# Alpha-Num_Single.net
KiCad netlist of a schematic drawn in EAGLE
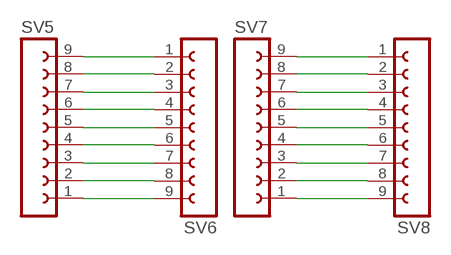
[diagram p0: schematic, sheet 1]

(export (version "E")
  (design (tool "Eeschema 10.0.6"))
  (components
    (comp (ref "SV5")
      (value "FE09-1")
      (footprint "eagle-import:FE09")
      (libsource (lib "eagle-import") (part "FE09-1"))
    )
    (comp (ref "SV6")
      (value "FE09-1")
      (footprint "eagle-import:FE09")
      (libsource (lib "eagle-import") (part "FE09-1"))
    )
    (comp (ref "SV7")
      (value "FE09-1")
      (footprint "eagle-import:FE09")
      (libsource (lib "eagle-import") (part "FE09-1"))
    )
    (comp (ref "SV8")
      (value "FE09-1")
      (footprint "eagle-import:FE09")
      (libsource (lib "eagle-import") (part "FE09-1"))
    )
  )
  (nets
    (net (code "1") (name "Net-(SV5-Pad1)") (class "Default")
      (node (ref "SV5") (pin "1") (pinfunction "1_1") (pintype "passive"))
      (node (ref "SV6") (pin "9") (pinfunction "9_9") (pintype "passive"))
    )
    (net (code "2") (name "Net-(SV5-Pad2)") (class "Default")
      (node (ref "SV5") (pin "2") (pinfunction "2_2") (pintype "passive"))
      (node (ref "SV6") (pin "8") (pinfunction "8_8") (pintype "passive"))
    )
    (net (code "3") (name "Net-(SV5-Pad3)") (class "Default")
      (node (ref "SV5") (pin "3") (pinfunction "3_3") (pintype "passive"))
      (node (ref "SV6") (pin "7") (pinfunction "7_7") (pintype "passive"))
    )
    (net (code "4") (name "Net-(SV5-Pad4)") (class "Default")
      (node (ref "SV5") (pin "4") (pinfunction "4_4") (pintype "passive"))
      (node (ref "SV6") (pin "6") (pinfunction "6_6") (pintype "passive"))
    )
    (net (code "5") (name "Net-(SV5-Pad5)") (class "Default")
      (node (ref "SV5") (pin "5") (pinfunction "5_5") (pintype "passive"))
      (node (ref "SV6") (pin "5") (pinfunction "5_5") (pintype "passive"))
    )
    (net (code "6") (name "Net-(SV5-Pad6)") (class "Default")
      (node (ref "SV5") (pin "6") (pinfunction "6_6") (pintype "passive"))
      (node (ref "SV6") (pin "4") (pinfunction "4_4") (pintype "passive"))
    )
    (net (code "7") (name "Net-(SV5-Pad7)") (class "Default")
      (node (ref "SV5") (pin "7") (pinfunction "7_7") (pintype "passive"))
      (node (ref "SV6") (pin "3") (pinfunction "3_3") (pintype "passive"))
    )
    (net (code "8") (name "Net-(SV5-Pad8)") (class "Default")
      (node (ref "SV5") (pin "8") (pinfunction "8_8") (pintype "passive"))
      (node (ref "SV6") (pin "2") (pinfunction "2_2") (pintype "passive"))
    )
    (net (code "9") (name "Net-(SV5-Pad9)") (class "Default")
      (node (ref "SV5") (pin "9") (pinfunction "9_9") (pintype "passive"))
      (node (ref "SV6") (pin "1") (pinfunction "1_1") (pintype "passive"))
    )
    (net (code "10") (name "Net-(SV7-Pad1)") (class "Default")
      (node (ref "SV7") (pin "1") (pinfunction "1_1") (pintype "passive"))
      (node (ref "SV8") (pin "9") (pinfunction "9_9") (pintype "passive"))
    )
    (net (code "11") (name "Net-(SV7-Pad2)") (class "Default")
      (node (ref "SV7") (pin "2") (pinfunction "2_2") (pintype "passive"))
      (node (ref "SV8") (pin "8") (pinfunction "8_8") (pintype "passive"))
    )
    (net (code "12") (name "Net-(SV7-Pad3)") (class "Default")
      (node (ref "SV7") (pin "3") (pinfunction "3_3") (pintype "passive"))
      (node (ref "SV8") (pin "7") (pinfunction "7_7") (pintype "passive"))
    )
    (net (code "13") (name "Net-(SV7-Pad4)") (class "Default")
      (node (ref "SV7") (pin "4") (pinfunction "4_4") (pintype "passive"))
      (node (ref "SV8") (pin "6") (pinfunction "6_6") (pintype "passive"))
    )
    (net (code "14") (name "Net-(SV7-Pad5)") (class "Default")
      (node (ref "SV7") (pin "5") (pinfunction "5_5") (pintype "passive"))
      (node (ref "SV8") (pin "5") (pinfunction "5_5") (pintype "passive"))
    )
    (net (code "15") (name "Net-(SV7-Pad6)") (class "Default")
      (node (ref "SV7") (pin "6") (pinfunction "6_6") (pintype "passive"))
      (node (ref "SV8") (pin "4") (pinfunction "4_4") (pintype "passive"))
    )
    (net (code "16") (name "Net-(SV7-Pad7)") (class "Default")
      (node (ref "SV7") (pin "7") (pinfunction "7_7") (pintype "passive"))
      (node (ref "SV8") (pin "3") (pinfunction "3_3") (pintype "passive"))
    )
    (net (code "17") (name "Net-(SV7-Pad8)") (class "Default")
      (node (ref "SV7") (pin "8") (pinfunction "8_8") (pintype "passive"))
      (node (ref "SV8") (pin "2") (pinfunction "2_2") (pintype "passive"))
    )
    (net (code "18") (name "Net-(SV7-Pad9)") (class "Default")
      (node (ref "SV7") (pin "9") (pinfunction "9_9") (pintype "passive"))
      (node (ref "SV8") (pin "1") (pinfunction "1_1") (pintype "passive"))
    )
  )
)
